# peripheral.net
KiCad netlist of a schematic drawn in EAGLE
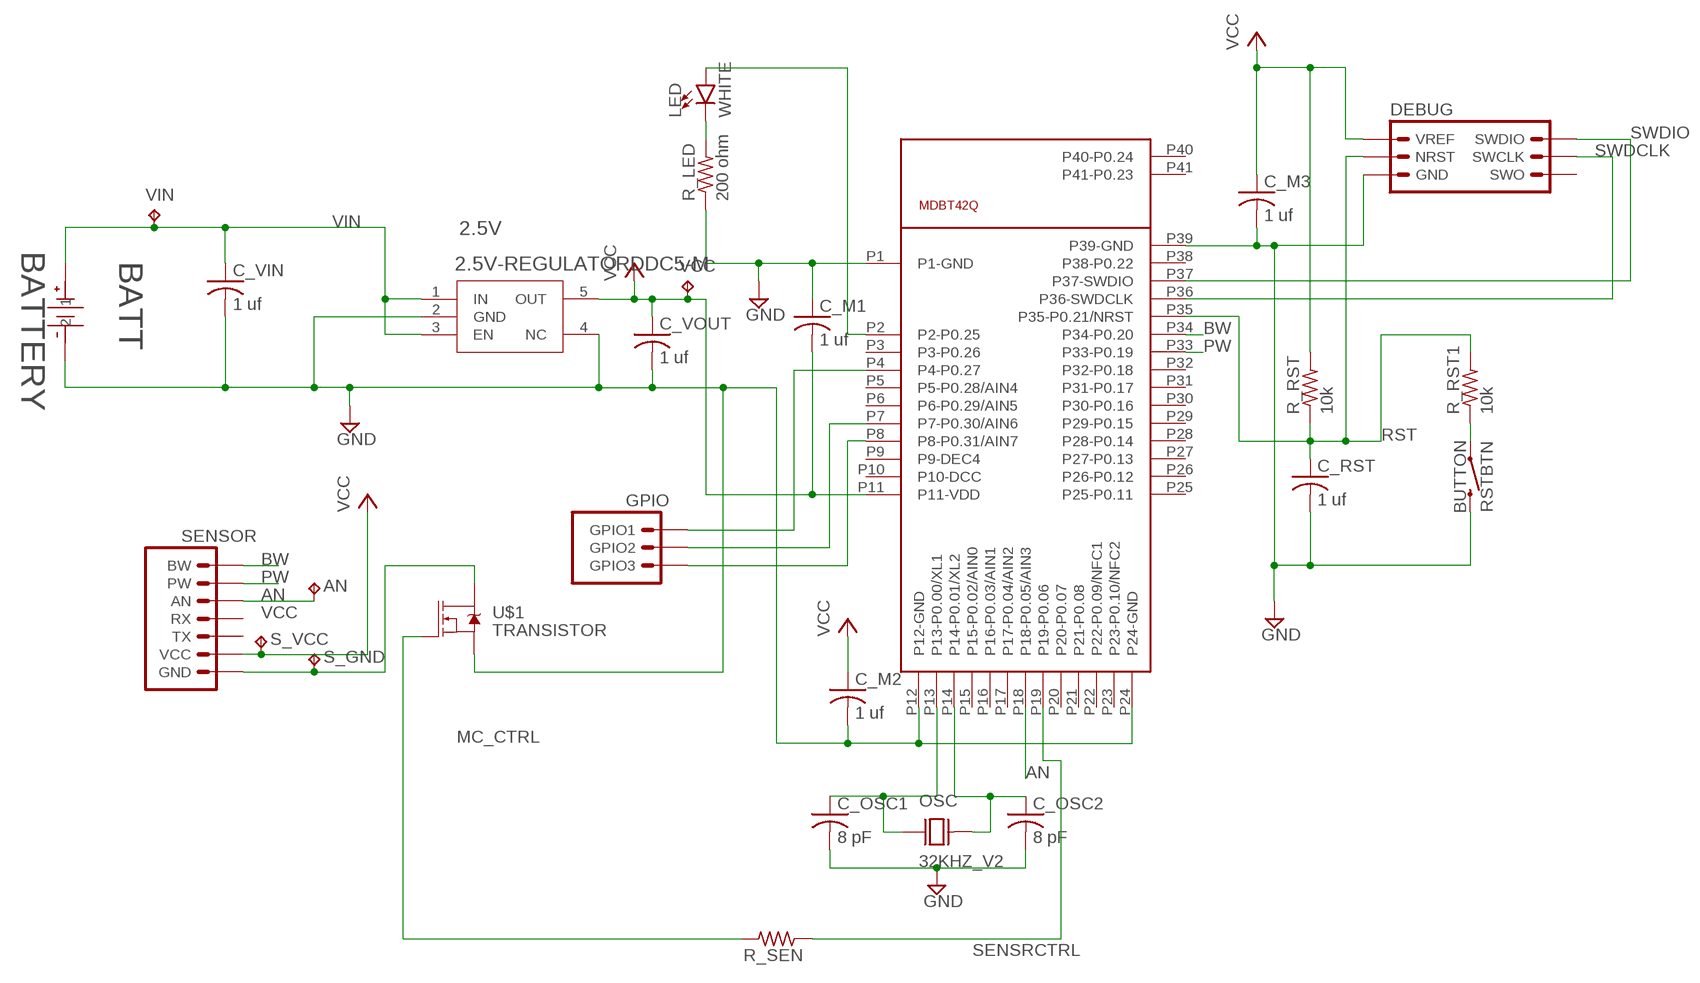
[diagram p0: schematic, sheet 1]

(export (version "E")
  (design (tool "Eeschema 10.0.6"))
  (components
    (comp (ref "2.5V")
      (value "2.5V-REGULATORDDC5-M")
      (footprint "eagle-import:DDC5-M")
      (fields (field (name "MANUFACTURER_PART_NUMBER") "TLV70025DDCR"))
      (libsource (lib "eagle-import") (part "2.5V-REGULATORDDC5-M"))
    )
    (comp (ref "AN")
      (value "TPTP11SQ")
      (footprint "eagle-import:TP11SQ")
      (libsource (lib "eagle-import") (part "TPTP11SQ"))
    )
    (comp (ref "BATT")
      (value "BATTERY")
      (footprint "eagle-import:BAT_HLDR_2468")
      (fields (field (name "MANUFACTURER_PART_NUMBER") "2468"))
      (libsource (lib "eagle-import") (part "BATTERY"))
    )
    (comp (ref "C_M1")
      (value "1 uf")
      (footprint "eagle-import:C0805K")
      (libsource (lib "eagle-import") (part "CAP"))
    )
    (comp (ref "C_M2")
      (value "1 uf")
      (footprint "eagle-import:C0805K")
      (libsource (lib "eagle-import") (part "CAP"))
    )
    (comp (ref "C_M3")
      (value "1 uf")
      (footprint "eagle-import:C0805K")
      (libsource (lib "eagle-import") (part "CAP"))
    )
    (comp (ref "C_OSC1")
      (value "8 pF")
      (footprint "eagle-import:C0805K")
      (libsource (lib "eagle-import") (part "CAP"))
    )
    (comp (ref "C_OSC2")
      (value "8 pF")
      (footprint "eagle-import:C0805K")
      (libsource (lib "eagle-import") (part "CAP"))
    )
    (comp (ref "C_RST")
      (value "1 uf")
      (footprint "eagle-import:C0805K")
      (libsource (lib "eagle-import") (part "CAP"))
    )
    (comp (ref "C_VIN")
      (value "1 uf")
      (footprint "eagle-import:C0805K")
      (libsource (lib "eagle-import") (part "CAP"))
    )
    (comp (ref "C_VOUT")
      (value "1 uf")
      (footprint "eagle-import:C0805K")
      (libsource (lib "eagle-import") (part "CAP"))
    )
    (comp (ref "DEBUG")
      (value "DEBUGGER")
      (footprint "eagle-import:MA03-2")
      (libsource (lib "eagle-import") (part "DEBUGGER"))
    )
    (comp (ref "GPIO")
      (value "GPIO")
      (footprint "eagle-import:MA03-1")
      (libsource (lib "eagle-import") (part "GPIO"))
    )
    (comp (ref "LED")
      (value "WHITE")
      (footprint "eagle-import:LED-1206")
      (libsource (lib "eagle-import") (part "LED_12061206"))
    )
    (comp (ref "MICRO")
      (value "MDBT42Q")
      (footprint "eagle-import:MDBT40")
      (libsource (lib "eagle-import") (part "MDBT42Q"))
    )
    (comp (ref "OSC")
      (value "32KHZ_V2")
      (footprint "eagle-import:XTAL_AB26TRB-32.768KHZ-T")
      (fields
        (field (name "DIGI-KEY_PART_NUMBER") "535-9033-1-ND")
        (field (name "MF") "Abracon")
        (field (name "MP") "AB26TRB-32.768KHZ-T")
      )
      (libsource (lib "eagle-import") (part "32KHZ_V2"))
    )
    (comp (ref "RSTBTN")
      (value "BUTTON")
      (footprint "eagle-import:TACTILE_SWITCH_SMD_6.2MM_TALL")
      (libsource (lib "eagle-import") (part "BUTTON"))
    )
    (comp (ref "R_LED")
      (value "200 ohm")
      (footprint "eagle-import:M0805")
      (libsource (lib "eagle-import") (part "RESISTOR"))
    )
    (comp (ref "R_RST")
      (value "10k")
      (footprint "eagle-import:M0805")
      (libsource (lib "eagle-import") (part "RESISTOR"))
    )
    (comp (ref "R_RST1")
      (value "10k")
      (footprint "eagle-import:M0805")
      (libsource (lib "eagle-import") (part "RESISTOR"))
    )
    (comp (ref "R_SEN")
      (value "RESISTOR")
      (footprint "eagle-import:M0805")
      (libsource (lib "eagle-import") (part "RESISTOR"))
    )
    (comp (ref "SENSOR")
      (value "SENSORHEADER")
      (footprint "eagle-import:MA07-1")
      (libsource (lib "eagle-import") (part "SENSORHEADER"))
    )
    (comp (ref "S_GND")
      (value "TPTP11SQ")
      (footprint "eagle-import:TP11SQ")
      (libsource (lib "eagle-import") (part "TPTP11SQ"))
    )
    (comp (ref "S_VCC")
      (value "TPTP11SQ")
      (footprint "eagle-import:TP11SQ")
      (libsource (lib "eagle-import") (part "TPTP11SQ"))
    )
    (comp (ref "U$1")
      (value "TRANSISTOR")
      (footprint "eagle-import:SOT23-3")
      (libsource (lib "eagle-import") (part "TRANSISTOR"))
    )
    (comp (ref "VCC")
      (value "TPTP11SQ")
      (footprint "eagle-import:TP11SQ")
      (libsource (lib "eagle-import") (part "TPTP11SQ"))
    )
    (comp (ref "VIN")
      (value "TPTP11SQ")
      (footprint "eagle-import:TP11SQ")
      (libsource (lib "eagle-import") (part "TPTP11SQ"))
    )
  )
  (nets
    (net (code "1") (name "/AN") (class "Default")
      (node (ref "AN") (pin "TP") (pinfunction "TP_TP") (pintype "input"))
      (node (ref "MICRO") (pin "P18") (pinfunction "P18-P0.05/AIN3_P18") (pintype "bidirectional"))
      (node (ref "SENSOR") (pin "5") (pinfunction "AN_5") (pintype "passive"))
    )
    (net (code "2") (name "/BW") (class "Default")
      (node (ref "MICRO") (pin "P34") (pinfunction "P34-P0.20_P34") (pintype "bidirectional"))
      (node (ref "SENSOR") (pin "7") (pinfunction "BW_7") (pintype "passive"))
    )
    (net (code "3") (name "/MC_CTRL") (class "Default")
      (node (ref "R_SEN") (pin "2") (pinfunction "2_2") (pintype "passive"))
      (node (ref "U$1") (pin "1_G") (pinfunction "G_1_G") (pintype "bidirectional"))
    )
    (net (code "4") (name "/PW") (class "Default")
      (node (ref "MICRO") (pin "P33") (pinfunction "P33-P0.19_P33") (pintype "bidirectional"))
      (node (ref "SENSOR") (pin "6") (pinfunction "PW_6") (pintype "passive"))
    )
    (net (code "5") (name "/RST") (class "Default")
      (node (ref "C_RST") (pin "1") (pinfunction "1_1") (pintype "passive"))
      (node (ref "DEBUG") (pin "4") (pinfunction "NRST_4") (pintype "passive"))
      (node (ref "MICRO") (pin "P35") (pinfunction "P35-P0.21/NRST_P35") (pintype "bidirectional"))
      (node (ref "R_RST") (pin "1") (pinfunction "1_1") (pintype "passive"))
      (node (ref "R_RST1") (pin "2") (pinfunction "2_2") (pintype "passive"))
    )
    (net (code "6") (name "/SENSRCTRL") (class "Default")
      (node (ref "MICRO") (pin "P19") (pinfunction "P19-P0.06_P19") (pintype "bidirectional"))
      (node (ref "R_SEN") (pin "1") (pinfunction "1_1") (pintype "passive"))
    )
    (net (code "7") (name "/SWDCLK") (class "Default")
      (node (ref "DEBUG") (pin "3") (pinfunction "SWCLK_3") (pintype "passive"))
      (node (ref "MICRO") (pin "P36") (pinfunction "P36-SWDCLK_P36") (pintype "bidirectional"))
    )
    (net (code "8") (name "/SWDIO") (class "Default")
      (node (ref "DEBUG") (pin "5") (pinfunction "SWDIO_5") (pintype "passive"))
      (node (ref "MICRO") (pin "P37") (pinfunction "P37-SWDIO_P37") (pintype "bidirectional"))
    )
    (net (code "9") (name "/VIN") (class "Default")
      (node (ref "2.5V") (pin "1") (pinfunction "IN_1") (pintype "input"))
      (node (ref "2.5V") (pin "3") (pinfunction "EN_3") (pintype "passive"))
      (node (ref "BATT") (pin "1") (pinfunction "1_1") (pintype "passive"))
      (node (ref "C_VIN") (pin "1") (pinfunction "1_1") (pintype "passive"))
      (node (ref "VIN") (pin "TP") (pinfunction "TP_TP") (pintype "input"))
    )
    (net (code "10") (name "GND") (class "Default")
      (node (ref "2.5V") (pin "2") (pinfunction "GND_2") (pintype "power_in"))
      (node (ref "2.5V") (pin "4") (pinfunction "NC_4") (pintype "passive"))
      (node (ref "BATT") (pin "2") (pinfunction "2_2") (pintype "passive"))
      (node (ref "BATT") (pin "3") (pinfunction "2_3") (pintype "passive"))
      (node (ref "BATT") (pin "4") (pinfunction "2_4") (pintype "passive"))
      (node (ref "C_M1") (pin "1") (pinfunction "1_1") (pintype "passive"))
      (node (ref "C_M2") (pin "2") (pinfunction "2_2") (pintype "passive"))
      (node (ref "C_M3") (pin "2") (pinfunction "2_2") (pintype "passive"))
      (node (ref "C_OSC1") (pin "2") (pinfunction "2_2") (pintype "passive"))
      (node (ref "C_OSC2") (pin "2") (pinfunction "2_2") (pintype "passive"))
      (node (ref "C_RST") (pin "2") (pinfunction "2_2") (pintype "passive"))
      (node (ref "C_VIN") (pin "2") (pinfunction "2_2") (pintype "passive"))
      (node (ref "C_VOUT") (pin "2") (pinfunction "2_2") (pintype "passive"))
      (node (ref "DEBUG") (pin "2") (pinfunction "GND_2") (pintype "passive"))
      (node (ref "MICRO") (pin "P1") (pinfunction "P1-GND_P1") (pintype "bidirectional"))
      (node (ref "MICRO") (pin "P12") (pinfunction "P12-GND_P12") (pintype "bidirectional"))
      (node (ref "MICRO") (pin "P24") (pinfunction "P24-GND_P24") (pintype "bidirectional"))
      (node (ref "MICRO") (pin "P39") (pinfunction "P39-GND_P39") (pintype "bidirectional"))
      (node (ref "RSTBTN") (pin "TOP1") (pinfunction "2_TOP1") (pintype "passive"))
      (node (ref "RSTBTN") (pin "TOP2") (pinfunction "2_TOP2") (pintype "passive"))
      (node (ref "R_LED") (pin "1") (pinfunction "1_1") (pintype "passive"))
      (node (ref "U$1") (pin "2_S") (pinfunction "S_2_S") (pintype "bidirectional"))
    )
    (net (code "11") (name "Net-(GPIO-GPIO1)") (class "Default")
      (node (ref "GPIO") (pin "3") (pinfunction "GPIO1_3") (pintype "passive"))
      (node (ref "MICRO") (pin "P4") (pinfunction "P4-P0.27_P4") (pintype "bidirectional"))
    )
    (net (code "12") (name "Net-(GPIO-GPIO2)") (class "Default")
      (node (ref "GPIO") (pin "2") (pinfunction "GPIO2_2") (pintype "passive"))
      (node (ref "MICRO") (pin "P7") (pinfunction "P7-P0.30/AIN6_P7") (pintype "bidirectional"))
    )
    (net (code "13") (name "Net-(GPIO-GPIO3)") (class "Default")
      (node (ref "GPIO") (pin "1") (pinfunction "GPIO3_1") (pintype "passive"))
      (node (ref "MICRO") (pin "P8") (pinfunction "P8-P0.31/AIN7_P8") (pintype "bidirectional"))
    )
    (net (code "14") (name "Net-(LED-PadC)") (class "Default")
      (node (ref "LED") (pin "C") (pinfunction "C_C") (pintype "passive"))
      (node (ref "R_LED") (pin "2") (pinfunction "2_2") (pintype "passive"))
    )
    (net (code "15") (name "Net-(MICRO-P2-P0.25)") (class "Default")
      (node (ref "LED") (pin "A") (pinfunction "A_A") (pintype "passive"))
      (node (ref "MICRO") (pin "P2") (pinfunction "P2-P0.25_P2") (pintype "bidirectional"))
    )
    (net (code "16") (name "Net-(MICRO-P13-P0.00{slash}XL1)") (class "Default")
      (node (ref "C_OSC1") (pin "1") (pinfunction "1_1") (pintype "passive"))
      (node (ref "MICRO") (pin "P13") (pinfunction "P13-P0.00/XL1_P13") (pintype "bidirectional"))
      (node (ref "OSC") (pin "P$3") (pinfunction "1_P$3") (pintype "passive"))
    )
    (net (code "17") (name "Net-(MICRO-P14-P0.01{slash}XL2)") (class "Default")
      (node (ref "C_OSC2") (pin "1") (pinfunction "1_1") (pintype "passive"))
      (node (ref "MICRO") (pin "P14") (pinfunction "P14-P0.01/XL2_P14") (pintype "bidirectional"))
      (node (ref "OSC") (pin "P$4") (pinfunction "2_P$4") (pintype "passive"))
    )
    (net (code "18") (name "Net-(RSTBTN-1-PadBOTTOM1)") (class "Default")
      (node (ref "RSTBTN") (pin "BOTTOM1") (pinfunction "1_BOTTOM1") (pintype "passive"))
      (node (ref "RSTBTN") (pin "BOTTOM2") (pinfunction "1_BOTTOM2") (pintype "passive"))
      (node (ref "R_RST1") (pin "1") (pinfunction "1_1") (pintype "passive"))
    )
    (net (code "19") (name "Net-(SENSOR-GND)") (class "Default")
      (node (ref "SENSOR") (pin "1") (pinfunction "GND_1") (pintype "passive"))
      (node (ref "S_GND") (pin "TP") (pinfunction "TP_TP") (pintype "input"))
      (node (ref "U$1") (pin "3_D") (pinfunction "D_3_D") (pintype "bidirectional"))
    )
    (net (code "20") (name "VCC") (class "Default")
      (node (ref "2.5V") (pin "5") (pinfunction "OUT_5") (pintype "output"))
      (node (ref "C_M1") (pin "2") (pinfunction "2_2") (pintype "passive"))
      (node (ref "C_M2") (pin "1") (pinfunction "1_1") (pintype "passive"))
      (node (ref "C_M3") (pin "1") (pinfunction "1_1") (pintype "passive"))
      (node (ref "C_VOUT") (pin "1") (pinfunction "1_1") (pintype "passive"))
      (node (ref "DEBUG") (pin "6") (pinfunction "VREF_6") (pintype "passive"))
      (node (ref "MICRO") (pin "P11") (pinfunction "P11-VDD_P11") (pintype "bidirectional"))
      (node (ref "R_RST") (pin "2") (pinfunction "2_2") (pintype "passive"))
      (node (ref "SENSOR") (pin "2") (pinfunction "VCC_2") (pintype "passive"))
      (node (ref "S_VCC") (pin "TP") (pinfunction "TP_TP") (pintype "input"))
      (node (ref "VCC") (pin "TP") (pinfunction "TP_TP") (pintype "input"))
    )
    (net (code "21") (name "unconnected-(DEBUG-SWO-Pad1)") (class "Default")
      (node (ref "DEBUG") (pin "1") (pinfunction "SWO_1") (pintype "passive"))
    )
    (net (code "22") (name "unconnected-(MICRO-P3-P0.26-PadP3)") (class "Default")
      (node (ref "MICRO") (pin "P3") (pinfunction "P3-P0.26_P3") (pintype "bidirectional"))
    )
    (net (code "23") (name "unconnected-(MICRO-P5-P0.28{slash}AIN4-PadP5)") (class "Default")
      (node (ref "MICRO") (pin "P5") (pinfunction "P5-P0.28/AIN4_P5") (pintype "bidirectional"))
    )
    (net (code "24") (name "unconnected-(MICRO-P6-P0.29{slash}AIN5-PadP6)") (class "Default")
      (node (ref "MICRO") (pin "P6") (pinfunction "P6-P0.29/AIN5_P6") (pintype "bidirectional"))
    )
    (net (code "25") (name "unconnected-(MICRO-P9-DEC4-PadP9)") (class "Default")
      (node (ref "MICRO") (pin "P9") (pinfunction "P9-DEC4_P9") (pintype "bidirectional"))
    )
    (net (code "26") (name "unconnected-(MICRO-P10-DCC-PadP10)") (class "Default")
      (node (ref "MICRO") (pin "P10") (pinfunction "P10-DCC_P10") (pintype "bidirectional"))
    )
    (net (code "27") (name "unconnected-(MICRO-P15-P0.02{slash}AIN0-PadP15)") (class "Default")
      (node (ref "MICRO") (pin "P15") (pinfunction "P15-P0.02/AIN0_P15") (pintype "bidirectional"))
    )
    (net (code "28") (name "unconnected-(MICRO-P16-P0.03{slash}AIN1-PadP16)") (class "Default")
      (node (ref "MICRO") (pin "P16") (pinfunction "P16-P0.03/AIN1_P16") (pintype "bidirectional"))
    )
    (net (code "29") (name "unconnected-(MICRO-P17-P0.04{slash}AIN2-PadP17)") (class "Default")
      (node (ref "MICRO") (pin "P17") (pinfunction "P17-P0.04/AIN2_P17") (pintype "bidirectional"))
    )
    (net (code "30") (name "unconnected-(MICRO-P20-P0.07-PadP20)") (class "Default")
      (node (ref "MICRO") (pin "P20") (pinfunction "P20-P0.07_P20") (pintype "bidirectional"))
    )
    (net (code "31") (name "unconnected-(MICRO-P21-P0.08-PadP21)") (class "Default")
      (node (ref "MICRO") (pin "P21") (pinfunction "P21-P0.08_P21") (pintype "bidirectional"))
    )
    (net (code "32") (name "unconnected-(MICRO-P22-P0.09{slash}NFC1-PadP22)") (class "Default")
      (node (ref "MICRO") (pin "P22") (pinfunction "P22-P0.09/NFC1_P22") (pintype "bidirectional"))
    )
    (net (code "33") (name "unconnected-(MICRO-P23-P0.10{slash}NFC2-PadP23)") (class "Default")
      (node (ref "MICRO") (pin "P23") (pinfunction "P23-P0.10/NFC2_P23") (pintype "bidirectional"))
    )
    (net (code "34") (name "unconnected-(MICRO-P25-P0.11-PadP25)") (class "Default")
      (node (ref "MICRO") (pin "P25") (pinfunction "P25-P0.11_P25") (pintype "bidirectional"))
    )
    (net (code "35") (name "unconnected-(MICRO-P26-P0.12-PadP26)") (class "Default")
      (node (ref "MICRO") (pin "P26") (pinfunction "P26-P0.12_P26") (pintype "bidirectional"))
    )
    (net (code "36") (name "unconnected-(MICRO-P27-P0.13-PadP27)") (class "Default")
      (node (ref "MICRO") (pin "P27") (pinfunction "P27-P0.13_P27") (pintype "bidirectional"))
    )
    (net (code "37") (name "unconnected-(MICRO-P28-P0.14-PadP28)") (class "Default")
      (node (ref "MICRO") (pin "P28") (pinfunction "P28-P0.14_P28") (pintype "bidirectional"))
    )
    (net (code "38") (name "unconnected-(MICRO-P29-P0.15-PadP29)") (class "Default")
      (node (ref "MICRO") (pin "P29") (pinfunction "P29-P0.15_P29") (pintype "bidirectional"))
    )
    (net (code "39") (name "unconnected-(MICRO-P30-P0.16-PadP30)") (class "Default")
      (node (ref "MICRO") (pin "P30") (pinfunction "P30-P0.16_P30") (pintype "bidirectional"))
    )
    (net (code "40") (name "unconnected-(MICRO-P31-P0.17-PadP31)") (class "Default")
      (node (ref "MICRO") (pin "P31") (pinfunction "P31-P0.17_P31") (pintype "bidirectional"))
    )
    (net (code "41") (name "unconnected-(MICRO-P32-P0.18-PadP32)") (class "Default")
      (node (ref "MICRO") (pin "P32") (pinfunction "P32-P0.18_P32") (pintype "bidirectional"))
    )
    (net (code "42") (name "unconnected-(MICRO-P38-P0.22-PadP38)") (class "Default")
      (node (ref "MICRO") (pin "P38") (pinfunction "P38-P0.22_P38") (pintype "bidirectional"))
    )
    (net (code "43") (name "unconnected-(MICRO-P40-P0.24-PadP40)") (class "Default")
      (node (ref "MICRO") (pin "P40") (pinfunction "P40-P0.24_P40") (pintype "bidirectional"))
    )
    (net (code "44") (name "unconnected-(MICRO-P41-P0.23-PadP41)") (class "Default")
      (node (ref "MICRO") (pin "P41") (pinfunction "P41-P0.23_P41") (pintype "bidirectional"))
    )
    (net (code "45") (name "unconnected-(SENSOR-RX-Pad4)") (class "Default")
      (node (ref "SENSOR") (pin "4") (pinfunction "RX_4") (pintype "passive"))
    )
    (net (code "46") (name "unconnected-(SENSOR-TX-Pad3)") (class "Default")
      (node (ref "SENSOR") (pin "3") (pinfunction "TX_3") (pintype "passive"))
    )
  )
)
